# Signal_conditioning.net
KiCad netlist of a schematic drawn in Altium Designer
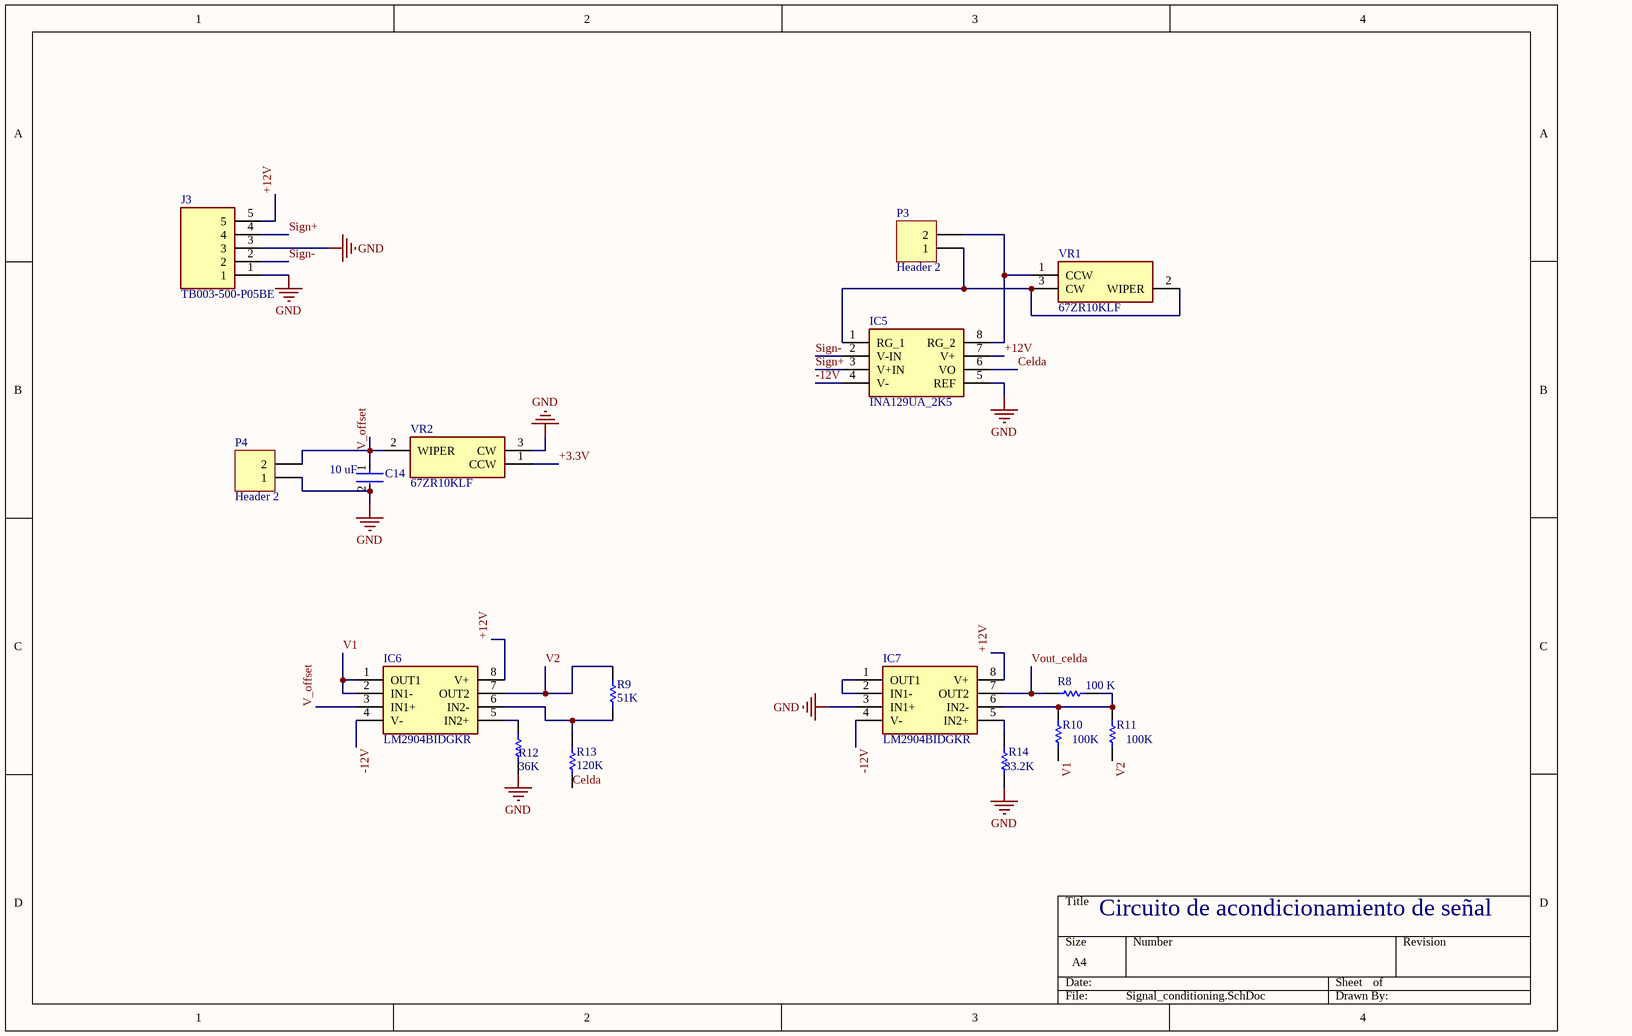
[diagram p0: Signal_conditioning.SchDoc]

(export (version "E")
  (design (tool "Eeschema 10.0.6"))
  (components
    (comp (ref "C14")
      (value "10 uF")
      (footprint "FP-GRM188-0_1-e0_2_0_55-MFG")
      (description "Chip Multilayer Ceramic Capacitors for General Purpose, 0603, 10uF, X6S, 22%, 20%, 2.5V")
      (fields (field (name "TOLERANCE") "20%") (field (name "VOLTAGE") "2.5V"))
      (libsource (lib "Altium Content Vault") (part "02cd4be3c70576c341d710602a673aa"))
    )
    (comp (ref "IC5")
      (value "INA129UA_2K5")
      (footprint "SamacSys:SOIC127P600X175-8N")
      (description "Integrated Circuit")
      (fields
        (field (name "MANUFACTURER_PART_NUMBER") "INA129UA/2K5")
        (field (name "MOUSER PART NUMBER") "595-INA129UA/2K5")
      )
      (libsource (lib "*") (part "INA129UA_2K5"))
    )
    (comp (ref "IC6")
      (value "LM2904BIDGKR")
      (footprint "SamacSys:SOP65P490X110-8N")
      (description "Integrated Circuit")
      (fields (field (name "MOUSER PART NUMBER") "595-LM2904BIDGKR"))
      (libsource (lib "*") (part "LM2904BIDGKR"))
    )
    (comp (ref "IC7")
      (value "LM2904BIDGKR")
      (footprint "SamacSys:SOP65P490X110-8N")
      (description "Integrated Circuit")
      (fields (field (name "MOUSER PART NUMBER") "595-LM2904BIDGKR"))
      (libsource (lib "*") (part "LM2904BIDGKR"))
    )
    (comp (ref "J3")
      (value "TB003-500-P05BE")
      (footprint "SamacSys:TB003500P05BE")
      (description "Connector")
      (fields (field (name "MOUSER PART NUMBER") "490-TB003-500-P05BE"))
      (libsource (lib "*") (part "TB003-500-P05BE"))
    )
    (comp (ref "P3")
      (value "Header 2")
      (footprint "HDR1X2")
      (description "Header, 2-Pin")
      (fields (field (name "PUBLISHER") "Altium Limited"))
      (libsource (lib "Miscellaneous Connectors") (part "Header 2"))
    )
    (comp (ref "P4")
      (value "Header 2")
      (footprint "HDR1X2")
      (description "Header, 2-Pin")
      (fields (field (name "PUBLISHER") "Altium Limited"))
      (libsource (lib "Miscellaneous Connectors") (part "Header 2"))
    )
    (comp (ref "R8")
      (value "100 K")
      (footprint "RESC1608X55X30NL15T15")
      (fields (field (name "MANUFACTURER") "Panasonic") (field (name "PART NUMBER") "ERJ-3GEYJ104V"))
      (libsource (lib "Altium Content Vault") (part "RES"))
    )
    (comp (ref "R9")
      (value "51K")
      (footprint "RESC1608X55X30ML20T20")
      (fields (field (name "PART NUMBER") "ERA3AEB333V") (field (name "MANUFACTURER") "Panasonic"))
      (libsource (lib "Altium Content Vault") (part "RES"))
    )
    (comp (ref "R10")
      (value "100K")
      (footprint "RESC1608X55X30NL15T15")
      (fields (field (name "MANUFACTURER") "Panasonic") (field (name "PART NUMBER") "ERJ-3GEYJ104V"))
      (libsource (lib "Altium Content Vault") (part "RES"))
    )
    (comp (ref "R11")
      (value "100K")
      (footprint "RESC1608X55X30NL15T15")
      (fields (field (name "MANUFACTURER") "Panasonic") (field (name "PART NUMBER") "ERJ-3GEYJ104V"))
      (libsource (lib "Altium Content Vault") (part "RES"))
    )
    (comp (ref "R12")
      (value "36K")
      (footprint "RESC1608X55X30ML20T20")
      (fields (field (name "PART NUMBER") "ERA3AEB333V") (field (name "MANUFACTURER") "Panasonic"))
      (libsource (lib "Altium Content Vault") (part "RES"))
    )
    (comp (ref "R13")
      (value "120K")
      (footprint "RESC1608X55X30ML20T20")
      (fields (field (name "PART NUMBER") "ERA3AEB333V") (field (name "MANUFACTURER") "Panasonic"))
      (libsource (lib "Altium Content Vault") (part "RES"))
    )
    (comp (ref "R14")
      (value "33.2K")
      (footprint "RESC1608X55X30NL15T15")
      (fields (field (name "MANUFACTURER") "Panasonic") (field (name "PART NUMBER") "ERJ-3GEYJ104V"))
      (libsource (lib "Altium Content Vault") (part "RES"))
    )
    (comp (ref "VR1")
      (value "67ZR10KLF")
      (footprint "SamacSys:67ZR10KLF")
      (description "Variable Resistor")
      (fields (field (name "MOUSER PART NUMBER") "858-67ZR10KLF"))
      (libsource (lib "*") (part "67ZR10KLF"))
    )
    (comp (ref "VR2")
      (value "67ZR10KLF")
      (footprint "SamacSys:67ZR10KLF")
      (description "Variable Resistor")
      (fields (field (name "MOUSER PART NUMBER") "858-67ZR10KLF"))
      (libsource (lib "") (part "67ZR10KLF_1"))
    )
  )
  (nets
    (net (code "1") (name "/+3.3V") (class "Default")
      (node (ref "VR2") (pin "1") (pinfunction "CCW_1") (pintype "passive"))
    )
    (net (code "2") (name "/+12V") (class "Default")
      (node (ref "IC5") (pin "7") (pinfunction "V+_7") (pintype "passive"))
      (node (ref "IC6") (pin "8") (pinfunction "V+_8") (pintype "passive"))
      (node (ref "IC7") (pin "8") (pinfunction "V+_8") (pintype "passive"))
      (node (ref "J3") (pin "5") (pinfunction "5_5") (pintype "passive"))
    )
    (net (code "3") (name "/-12V") (class "Default")
      (node (ref "IC5") (pin "4") (pinfunction "V-_4") (pintype "passive"))
      (node (ref "IC6") (pin "4") (pinfunction "V-_4") (pintype "passive"))
      (node (ref "IC7") (pin "4") (pinfunction "V-_4") (pintype "passive"))
    )
    (net (code "4") (name "/Celda") (class "Default")
      (node (ref "IC5") (pin "6") (pinfunction "VO_6") (pintype "passive"))
      (node (ref "R13") (pin "1") (pinfunction "1_1") (pintype "passive"))
    )
    (net (code "5") (name "/Sign+") (class "Default")
      (node (ref "IC5") (pin "3") (pinfunction "V+IN_3") (pintype "passive"))
      (node (ref "J3") (pin "4") (pinfunction "4_4") (pintype "passive"))
    )
    (net (code "6") (name "/Sign-") (class "Default")
      (node (ref "IC5") (pin "2") (pinfunction "V-IN_2") (pintype "passive"))
      (node (ref "J3") (pin "2") (pinfunction "2_2") (pintype "passive"))
    )
    (net (code "7") (name "/V1") (class "Default")
      (node (ref "IC6") (pin "1") (pinfunction "OUT1_1") (pintype "passive"))
      (node (ref "IC6") (pin "2") (pinfunction "IN1-_2") (pintype "passive"))
      (node (ref "R10") (pin "1") (pinfunction "1_1") (pintype "passive"))
    )
    (net (code "8") (name "/V2") (class "Default")
      (node (ref "IC6") (pin "7") (pinfunction "OUT2_7") (pintype "passive"))
      (node (ref "R11") (pin "1") (pinfunction "1_1") (pintype "passive"))
      (node (ref "R9") (pin "2") (pinfunction "2_2") (pintype "passive"))
    )
    (net (code "9") (name "/V_offset") (class "Default")
      (node (ref "C14") (pin "1") (pinfunction "1_1") (pintype "passive"))
      (node (ref "IC6") (pin "3") (pinfunction "IN1+_3") (pintype "passive"))
      (node (ref "P4") (pin "2") (pinfunction "2_2") (pintype "passive"))
      (node (ref "VR2") (pin "2") (pinfunction "WIPER_2") (pintype "passive"))
    )
    (net (code "10") (name "/Vout_celda") (class "Default")
      (node (ref "IC7") (pin "7") (pinfunction "OUT2_7") (pintype "passive"))
      (node (ref "R8") (pin "2") (pinfunction "2_2") (pintype "passive"))
    )
    (net (code "11") (name "GND") (class "Default")
      (node (ref "C14") (pin "2") (pinfunction "2_2") (pintype "passive"))
      (node (ref "IC5") (pin "5") (pinfunction "REF_5") (pintype "passive"))
      (node (ref "IC7") (pin "3") (pinfunction "IN1+_3") (pintype "passive"))
      (node (ref "J3") (pin "1") (pinfunction "1_1") (pintype "passive"))
      (node (ref "J3") (pin "3") (pinfunction "3_3") (pintype "passive"))
      (node (ref "P4") (pin "1") (pinfunction "1_1") (pintype "passive"))
      (node (ref "R12") (pin "1") (pinfunction "1_1") (pintype "passive"))
      (node (ref "R14") (pin "1") (pinfunction "1_1") (pintype "passive"))
      (node (ref "VR2") (pin "3") (pinfunction "CW_3") (pintype "passive"))
    )
    (net (code "12") (name "Net-(IC5-RG_1)") (class "Default")
      (node (ref "IC5") (pin "1") (pinfunction "RG_1_1") (pintype "passive"))
      (node (ref "P3") (pin "1") (pinfunction "1_1") (pintype "passive"))
      (node (ref "VR1") (pin "2") (pinfunction "WIPER_2") (pintype "passive"))
      (node (ref "VR1") (pin "3") (pinfunction "CW_3") (pintype "passive"))
    )
    (net (code "13") (name "Net-(IC5-RG_2)") (class "Default")
      (node (ref "IC5") (pin "8") (pinfunction "RG_2_8") (pintype "passive"))
      (node (ref "P3") (pin "2") (pinfunction "2_2") (pintype "passive"))
      (node (ref "VR1") (pin "1") (pinfunction "CCW_1") (pintype "passive"))
    )
    (net (code "14") (name "Net-(IC6-IN2+)") (class "Default")
      (node (ref "IC6") (pin "5") (pinfunction "IN2+_5") (pintype "passive"))
      (node (ref "R12") (pin "2") (pinfunction "2_2") (pintype "passive"))
    )
    (net (code "15") (name "Net-(IC6-IN2-)") (class "Default")
      (node (ref "IC6") (pin "6") (pinfunction "IN2-_6") (pintype "passive"))
      (node (ref "R13") (pin "2") (pinfunction "2_2") (pintype "passive"))
      (node (ref "R9") (pin "1") (pinfunction "1_1") (pintype "passive"))
    )
    (net (code "16") (name "Net-(IC7-IN1-)") (class "Default")
      (node (ref "IC7") (pin "1") (pinfunction "OUT1_1") (pintype "passive"))
      (node (ref "IC7") (pin "2") (pinfunction "IN1-_2") (pintype "passive"))
    )
    (net (code "17") (name "Net-(IC7-IN2+)") (class "Default")
      (node (ref "IC7") (pin "5") (pinfunction "IN2+_5") (pintype "passive"))
      (node (ref "R14") (pin "2") (pinfunction "2_2") (pintype "passive"))
    )
    (net (code "18") (name "Net-(IC7-IN2-)") (class "Default")
      (node (ref "IC7") (pin "6") (pinfunction "IN2-_6") (pintype "passive"))
      (node (ref "R10") (pin "2") (pinfunction "2_2") (pintype "passive"))
      (node (ref "R11") (pin "2") (pinfunction "2_2") (pintype "passive"))
      (node (ref "R8") (pin "1") (pinfunction "1_1") (pintype "passive"))
    )
  )
)
